# ethernet_module.net
KiCad netlist of a schematic drawn in Altium Designer
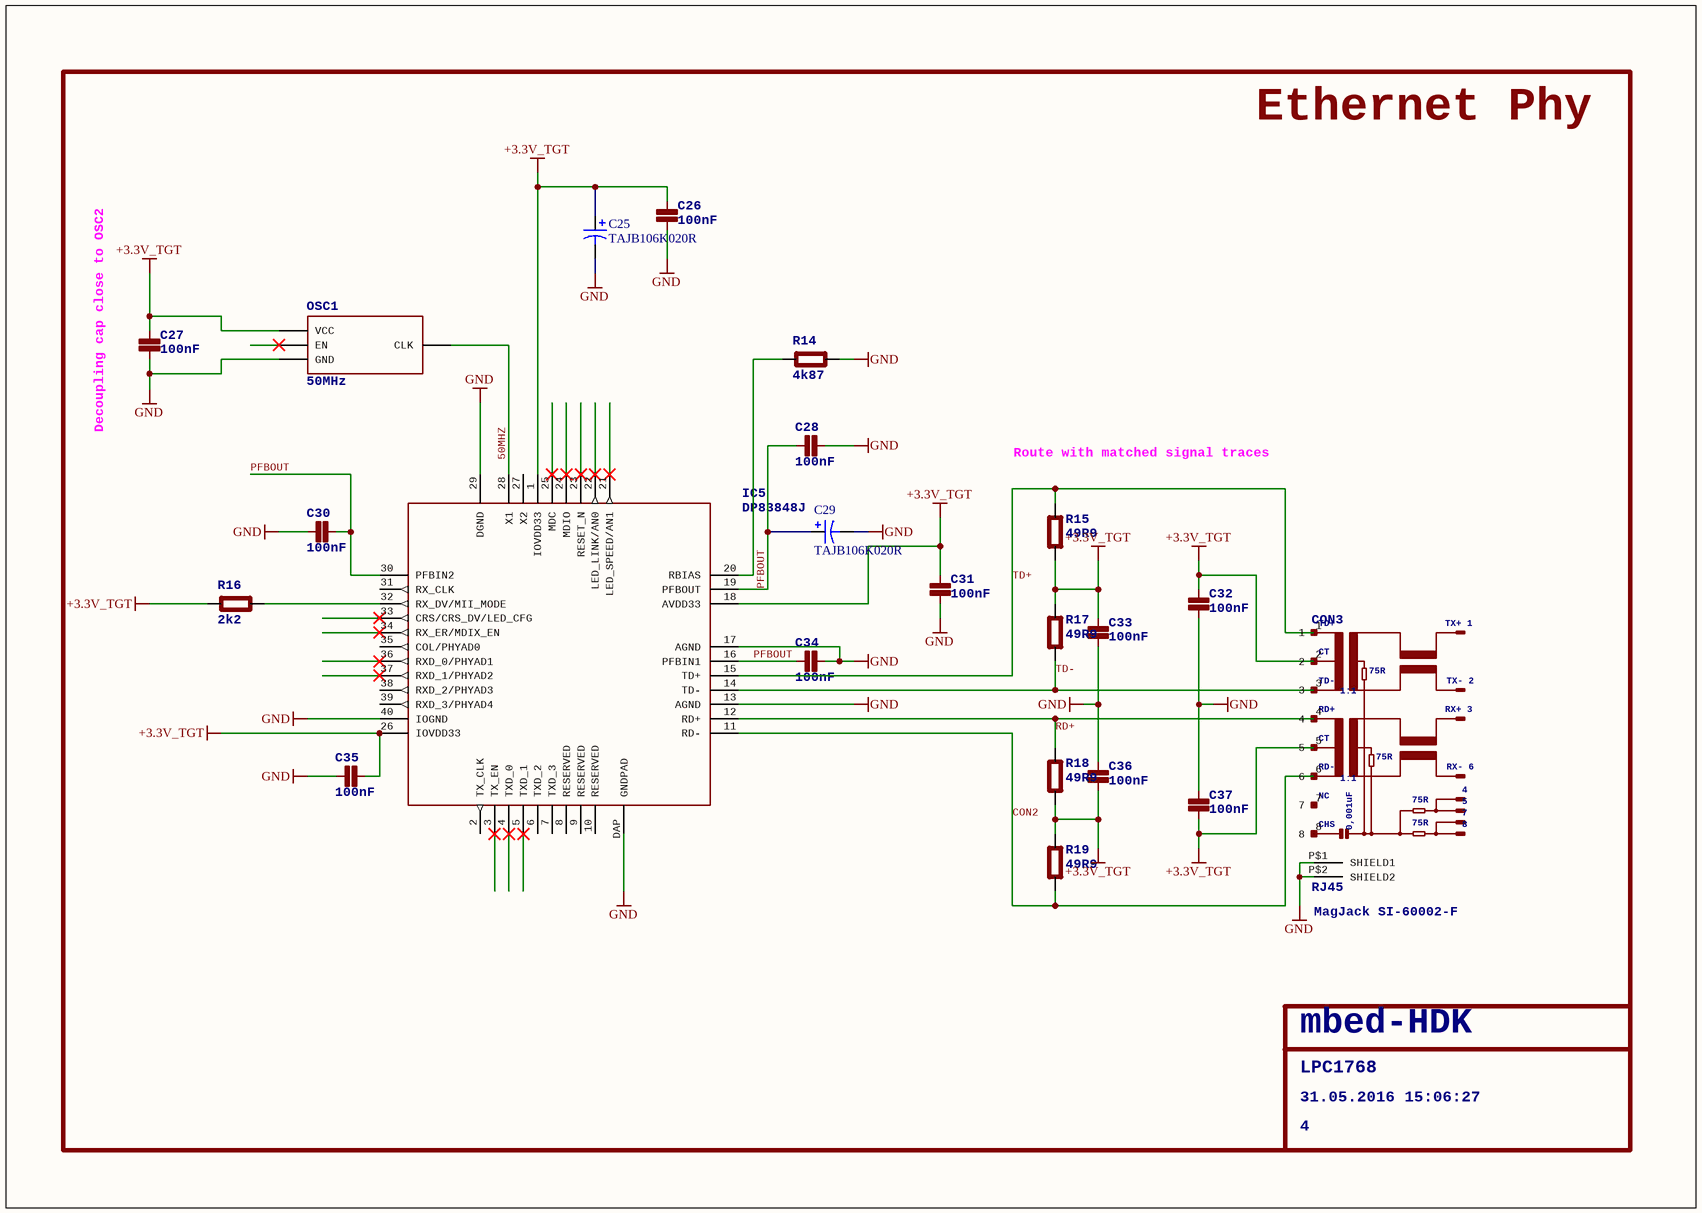
[diagram p0: ethernet_module.SchDoc]

(export (version "E")
  (design (tool "Eeschema 10.0.6"))
  (components
    (comp (ref "C25")
      (value "TAJB106K020R")
      (footprint "AVX-CAPC3528_V")
      (description "Capacitor, Tantalum, 10uF 10% 20V MCCT-B (3528)")
      (fields (field (name "MANUFACTURER") "AVX") (field (name "TOLERANCE") "10%"))
      (libsource (lib "Altium Content Vault") (part "CMP-0279-00001-1"))
    )
    (comp (ref "C26") (value "100nF") (footprint "0603") (libsource (lib "") (part "C0603_1")))
    (comp (ref "C27") (value "100nF") (footprint "0603") (libsource (lib "") (part "C0603_1")))
    (comp (ref "C28") (value "100nF") (footprint "0603") (libsource (lib "mbed-HDK") (part "C0603")))
    (comp (ref "C29")
      (value "TAJB106K020R")
      (footprint "AVX-CAPC3528_V")
      (description "Capacitor, Tantalum, 10uF 10% 20V MCCT-B (3528)")
      (fields (field (name "MANUFACTURER") "AVX") (field (name "TOLERANCE") "10%"))
      (libsource (lib "Altium Content Vault") (part "AVX-CAP-P-2"))
    )
    (comp (ref "C30") (value "100nF") (footprint "0603") (libsource (lib "") (part "C0603_2")))
    (comp (ref "C31") (value "100nF") (footprint "0603") (libsource (lib "") (part "C0603_1")))
    (comp (ref "C32") (value "100nF") (footprint "0603") (libsource (lib "") (part "C0603_1")))
    (comp (ref "C33") (value "100nF") (footprint "0603") (libsource (lib "") (part "C0603_1")))
    (comp (ref "C34") (value "100nF") (footprint "0603") (libsource (lib "") (part "C0603_2")))
    (comp (ref "C35") (value "100nF") (footprint "0603") (libsource (lib "mbed-HDK") (part "C0603")))
    (comp (ref "C36") (value "100nF") (footprint "0603") (libsource (lib "") (part "C0603_1")))
    (comp (ref "C37") (value "100nF") (footprint "0603") (libsource (lib "") (part "C0603_1")))
    (comp (ref "CON3")
      (value "RJ45")
      (footprint "RJ45")
      (description "Magjack SI-68002")
      (fields
        (field (name "75R") "75R")
        (field (name "75R_1") "75R")
        (field (name "75R_2") "75R")
        (field (name "75R_3") "75R")
        (field (name "TD+") "TD+")
        (field (name "CT") "CT")
        (field (name "TD-") "TD-")
        (field (name "RD+") "RD+")
        (field (name "CT_1") "CT")
        (field (name "RD-") "RD-")
        (field (name "NC") "NC")
        (field (name "CHS") "CHS")
        (field (name "0,001UF") "0,001uF")
        (field (name "RX+3") "RX+ 3")
        (field (name "TX-2") "TX- 2")
        (field (name "TX+1") "TX+ 1")
        (field (name "RX-6") "RX- 6")
        (field (name "4") "4")
        (field (name "5") "5")
        (field (name "7") "7")
        (field (name "8") "8")
        (field (name "1:1") "1:1")
        (field (name "1:1_1") "1:1")
        (field (name "MAGJACKSI-60002-F") "MagJack SI-60002-F")
      )
      (libsource (lib "mbed-HDK") (part "RJ45"))
    )
    (comp (ref "IC5")
      (value "DP83848J")
      (footprint "LLP-40")
      (description "National Semiconductor DP83848J PHYTER Mini LS Single Port 10/100 Ethernet Transceiver")
      (libsource (lib "mbed-HDK") (part "DP83848J"))
    )
    (comp (ref "OSC1")
      (value "50MHz")
      (footprint "3.2X.2.5")
      (libsource (lib "mbed-HDK") (part "OSCILLATOR"))
    )
    (comp (ref "R14") (value "4k87") (footprint "0603") (libsource (lib "mbed-HDK") (part "R0603")))
    (comp (ref "R15") (value "49R9") (footprint "0603") (libsource (lib "mbed-HDK") (part "R0603")))
    (comp (ref "R16") (value "2k2") (footprint "0603") (libsource (lib "mbed-HDK") (part "R0603")))
    (comp (ref "R17") (value "49R9") (footprint "0603") (libsource (lib "mbed-HDK") (part "R0603")))
    (comp (ref "R18") (value "49R9") (footprint "0603") (libsource (lib "mbed-HDK") (part "R0603")))
    (comp (ref "R19") (value "49R9") (footprint "0603") (libsource (lib "mbed-HDK") (part "R0603")))
  )
  (nets
    (net (code "1") (name "+3.3V_TGT") (class "Default")
      (node (ref "C25") (pin "1") (pinfunction "1_1") (pintype "passive"))
      (node (ref "C26") (pin "1") (pinfunction "P$1_1") (pintype "passive"))
      (node (ref "C27") (pin "1") (pinfunction "P$1_1") (pintype "passive"))
      (node (ref "C31") (pin "1") (pinfunction "P$1_1") (pintype "passive"))
      (node (ref "C32") (pin "1") (pinfunction "P$1_1") (pintype "passive"))
      (node (ref "C33") (pin "1") (pinfunction "P$1_1") (pintype "passive"))
      (node (ref "C35") (pin "1") (pinfunction "P$1_1") (pintype "passive"))
      (node (ref "C36") (pin "2") (pinfunction "P$2_2") (pintype "passive"))
      (node (ref "C37") (pin "2") (pinfunction "P$2_2") (pintype "passive"))
      (node (ref "CON3") (pin "2") (pinfunction "2_2") (pintype "passive"))
      (node (ref "CON3") (pin "5") (pinfunction "5_5") (pintype "passive"))
      (node (ref "IC5") (pin "1") (pinfunction "IOVDD33_1") (pintype "power_in"))
      (node (ref "IC5") (pin "18") (pinfunction "AVDD33_18") (pintype "power_in"))
      (node (ref "IC5") (pin "26") (pinfunction "IOVDD33_26") (pintype "power_in"))
      (node (ref "OSC1") (pin "P$4") (pinfunction "VCC_P$4") (pintype "passive"))
      (node (ref "R15") (pin "1") (pinfunction "P$1_1") (pintype "passive"))
      (node (ref "R16") (pin "1") (pinfunction "P$1_1") (pintype "passive"))
      (node (ref "R17") (pin "2") (pinfunction "P$2_2") (pintype "passive"))
      (node (ref "R18") (pin "1") (pinfunction "P$1_1") (pintype "passive"))
      (node (ref "R19") (pin "2") (pinfunction "P$2_2") (pintype "passive"))
    )
    (net (code "2") (name "/50MHZ") (class "Default")
      (node (ref "IC5") (pin "28") (pinfunction "X1_28") (pintype "passive"))
      (node (ref "OSC1") (pin "P$3") (pinfunction "CLK_P$3") (pintype "passive"))
    )
    (net (code "3") (name "/CON2") (class "Default")
      (node (ref "CON3") (pin "6") (pinfunction "6_6") (pintype "passive"))
      (node (ref "IC5") (pin "11") (pinfunction "RD-_11") (pintype "passive"))
      (node (ref "R19") (pin "1") (pinfunction "P$1_1") (pintype "passive"))
    )
    (net (code "4") (name "/PFBOUT") (class "Default")
      (node (ref "C28") (pin "2") (pinfunction "P$2_2") (pintype "passive"))
      (node (ref "C29") (pin "1") (pinfunction "1_1") (pintype "passive"))
      (node (ref "C30") (pin "2") (pinfunction "P$2_2") (pintype "passive"))
      (node (ref "C34") (pin "1") (pinfunction "P$1_1") (pintype "passive"))
      (node (ref "IC5") (pin "16") (pinfunction "PFBIN1_16") (pintype "passive"))
      (node (ref "IC5") (pin "19") (pinfunction "PFBOUT_19") (pintype "passive"))
      (node (ref "IC5") (pin "30") (pinfunction "PFBIN2_30") (pintype "passive"))
    )
    (net (code "5") (name "/RD+") (class "Default")
      (node (ref "CON3") (pin "4") (pinfunction "4_4") (pintype "passive"))
      (node (ref "IC5") (pin "12") (pinfunction "RD+_12") (pintype "passive"))
      (node (ref "R18") (pin "2") (pinfunction "P$2_2") (pintype "passive"))
    )
    (net (code "6") (name "/TD+") (class "Default")
      (node (ref "CON3") (pin "1") (pinfunction "1_1") (pintype "passive"))
      (node (ref "IC5") (pin "15") (pinfunction "TD+_15") (pintype "passive"))
      (node (ref "R15") (pin "2") (pinfunction "P$2_2") (pintype "passive"))
    )
    (net (code "7") (name "/TD-") (class "Default")
      (node (ref "CON3") (pin "3") (pinfunction "3_3") (pintype "passive"))
      (node (ref "IC5") (pin "14") (pinfunction "TD-_14") (pintype "passive"))
      (node (ref "R17") (pin "1") (pinfunction "P$1_1") (pintype "passive"))
    )
    (net (code "8") (name "GND") (class "Default")
      (node (ref "C25") (pin "2") (pinfunction "2_2") (pintype "passive"))
      (node (ref "C26") (pin "2") (pinfunction "P$2_2") (pintype "passive"))
      (node (ref "C27") (pin "2") (pinfunction "P$2_2") (pintype "passive"))
      (node (ref "C28") (pin "1") (pinfunction "P$1_1") (pintype "passive"))
      (node (ref "C29") (pin "2") (pinfunction "2_2") (pintype "passive"))
      (node (ref "C30") (pin "1") (pinfunction "P$1_1") (pintype "passive"))
      (node (ref "C31") (pin "2") (pinfunction "P$2_2") (pintype "passive"))
      (node (ref "C32") (pin "2") (pinfunction "P$2_2") (pintype "passive"))
      (node (ref "C33") (pin "2") (pinfunction "P$2_2") (pintype "passive"))
      (node (ref "C34") (pin "2") (pinfunction "P$2_2") (pintype "passive"))
      (node (ref "C35") (pin "2") (pinfunction "P$2_2") (pintype "passive"))
      (node (ref "C36") (pin "1") (pinfunction "P$1_1") (pintype "passive"))
      (node (ref "C37") (pin "1") (pinfunction "P$1_1") (pintype "passive"))
      (node (ref "CON3") (pin "P$1") (pinfunction "SHIELD1_P$1") (pintype "passive"))
      (node (ref "CON3") (pin "P$2") (pinfunction "SHIELD2_P$2") (pintype "passive"))
      (node (ref "IC5") (pin "13") (pinfunction "AGND_13") (pintype "power_in"))
      (node (ref "IC5") (pin "17") (pinfunction "AGND_17") (pintype "power_in"))
      (node (ref "IC5") (pin "29") (pinfunction "DGND_29") (pintype "power_in"))
      (node (ref "IC5") (pin "40") (pinfunction "IOGND_40") (pintype "power_in"))
      (node (ref "IC5") (pin "DAP") (pinfunction "GNDPAD_DAP") (pintype "power_in"))
      (node (ref "OSC1") (pin "P$2") (pinfunction "GND_P$2") (pintype "passive"))
      (node (ref "R14") (pin "1") (pinfunction "P$1_1") (pintype "passive"))
    )
    (net (code "9") (name "Net-(IC5-RBIAS)") (class "Default")
      (node (ref "IC5") (pin "20") (pinfunction "RBIAS_20") (pintype "passive"))
      (node (ref "R14") (pin "2") (pinfunction "P$2_2") (pintype "passive"))
    )
    (net (code "10") (name "Net-(IC5-RX_DV{slash}MII_MODE)") (class "Default")
      (node (ref "IC5") (pin "32") (pinfunction "RX_DV/MII_MODE_32") (pintype "output"))
      (node (ref "R16") (pin "2") (pinfunction "P$2_2") (pintype "passive"))
    )
    (net (code "11") (name "unconnected-(CON3-Pad7)") (class "Default")
      (node (ref "CON3") (pin "7") (pinfunction "7_7") (pintype "passive"))
    )
    (net (code "12") (name "unconnected-(CON3-Pad8)") (class "Default")
      (node (ref "CON3") (pin "8") (pinfunction "8_8") (pintype "passive"))
    )
    (net (code "13") (name "unconnected-(IC5-COL{slash}PHYAD0-Pad35)") (class "Default")
      (node (ref "IC5") (pin "35") (pinfunction "COL/PHYAD0_35") (pintype "output"))
    )
    (net (code "14") (name "unconnected-(IC5-CRS{slash}CRS_DV{slash}LED_CFG-Pad33)") (class "Default")
      (node (ref "IC5") (pin "33") (pinfunction "CRS/CRS_DV/LED_CFG_33") (pintype "output+no_connect"))
    )
    (net (code "15") (name "unconnected-(IC5-LED_LINK{slash}AN0-Pad22)") (class "Default")
      (node (ref "IC5") (pin "22") (pinfunction "LED_LINK/AN0_22") (pintype "output+no_connect"))
    )
    (net (code "16") (name "unconnected-(IC5-LED_SPEED{slash}AN1-Pad21)") (class "Default")
      (node (ref "IC5") (pin "21") (pinfunction "LED_SPEED/AN1_21") (pintype "output+no_connect"))
    )
    (net (code "17") (name "unconnected-(IC5-MDC-Pad25)") (class "Default")
      (node (ref "IC5") (pin "25") (pinfunction "MDC_25") (pintype "passive+no_connect"))
    )
    (net (code "18") (name "unconnected-(IC5-MDIO-Pad24)") (class "Default")
      (node (ref "IC5") (pin "24") (pinfunction "MDIO_24") (pintype "passive+no_connect"))
    )
    (net (code "19") (name "unconnected-(IC5-RESERVED-Pad8)") (class "Default")
      (node (ref "IC5") (pin "8") (pinfunction "RESERVED_8") (pintype "passive"))
    )
    (net (code "20") (name "unconnected-(IC5-RESERVED-Pad9)") (class "Default")
      (node (ref "IC5") (pin "9") (pinfunction "RESERVED_9") (pintype "passive"))
    )
    (net (code "21") (name "unconnected-(IC5-RESERVED-Pad10)") (class "Default")
      (node (ref "IC5") (pin "10") (pinfunction "RESERVED_10") (pintype "passive"))
    )
    (net (code "22") (name "unconnected-(IC5-RESET_N-Pad23)") (class "Default")
      (node (ref "IC5") (pin "23") (pinfunction "RESET_N_23") (pintype "passive+no_connect"))
    )
    (net (code "23") (name "unconnected-(IC5-RXD_0{slash}PHYAD1-Pad36)") (class "Default")
      (node (ref "IC5") (pin "36") (pinfunction "RXD_0/PHYAD1_36") (pintype "output+no_connect"))
    )
    (net (code "24") (name "unconnected-(IC5-RXD_1{slash}PHYAD2-Pad37)") (class "Default")
      (node (ref "IC5") (pin "37") (pinfunction "RXD_1/PHYAD2_37") (pintype "output+no_connect"))
    )
    (net (code "25") (name "unconnected-(IC5-RXD_2{slash}PHYAD3-Pad38)") (class "Default")
      (node (ref "IC5") (pin "38") (pinfunction "RXD_2/PHYAD3_38") (pintype "output"))
    )
    (net (code "26") (name "unconnected-(IC5-RXD_3{slash}PHYAD4-Pad39)") (class "Default")
      (node (ref "IC5") (pin "39") (pinfunction "RXD_3/PHYAD4_39") (pintype "output"))
    )
    (net (code "27") (name "unconnected-(IC5-RX_CLK-Pad31)") (class "Default")
      (node (ref "IC5") (pin "31") (pinfunction "RX_CLK_31") (pintype "output"))
    )
    (net (code "28") (name "unconnected-(IC5-RX_ER{slash}MDIX_EN-Pad34)") (class "Default")
      (node (ref "IC5") (pin "34") (pinfunction "RX_ER/MDIX_EN_34") (pintype "output+no_connect"))
    )
    (net (code "29") (name "unconnected-(IC5-TXD_0-Pad4)") (class "Default")
      (node (ref "IC5") (pin "4") (pinfunction "TXD_0_4") (pintype "passive+no_connect"))
    )
    (net (code "30") (name "unconnected-(IC5-TXD_1-Pad5)") (class "Default")
      (node (ref "IC5") (pin "5") (pinfunction "TXD_1_5") (pintype "passive+no_connect"))
    )
    (net (code "31") (name "unconnected-(IC5-TXD_2-Pad6)") (class "Default")
      (node (ref "IC5") (pin "6") (pinfunction "TXD_2_6") (pintype "passive"))
    )
    (net (code "32") (name "unconnected-(IC5-TXD_3-Pad7)") (class "Default")
      (node (ref "IC5") (pin "7") (pinfunction "TXD_3_7") (pintype "passive"))
    )
    (net (code "33") (name "unconnected-(IC5-TX_CLK-Pad2)") (class "Default")
      (node (ref "IC5") (pin "2") (pinfunction "TX_CLK_2") (pintype "output"))
    )
    (net (code "34") (name "unconnected-(IC5-TX_EN-Pad3)") (class "Default")
      (node (ref "IC5") (pin "3") (pinfunction "TX_EN_3") (pintype "passive+no_connect"))
    )
    (net (code "35") (name "unconnected-(IC5-X2-Pad27)") (class "Default")
      (node (ref "IC5") (pin "27") (pinfunction "X2_27") (pintype "passive"))
    )
    (net (code "36") (name "unconnected-(OSC1-EN-PadP$1)") (class "Default")
      (node (ref "OSC1") (pin "P$1") (pinfunction "EN_P$1") (pintype "passive+no_connect"))
    )
  )
)
